# Chessbot_v5.net
KiCad netlist of a schematic drawn in EAGLE
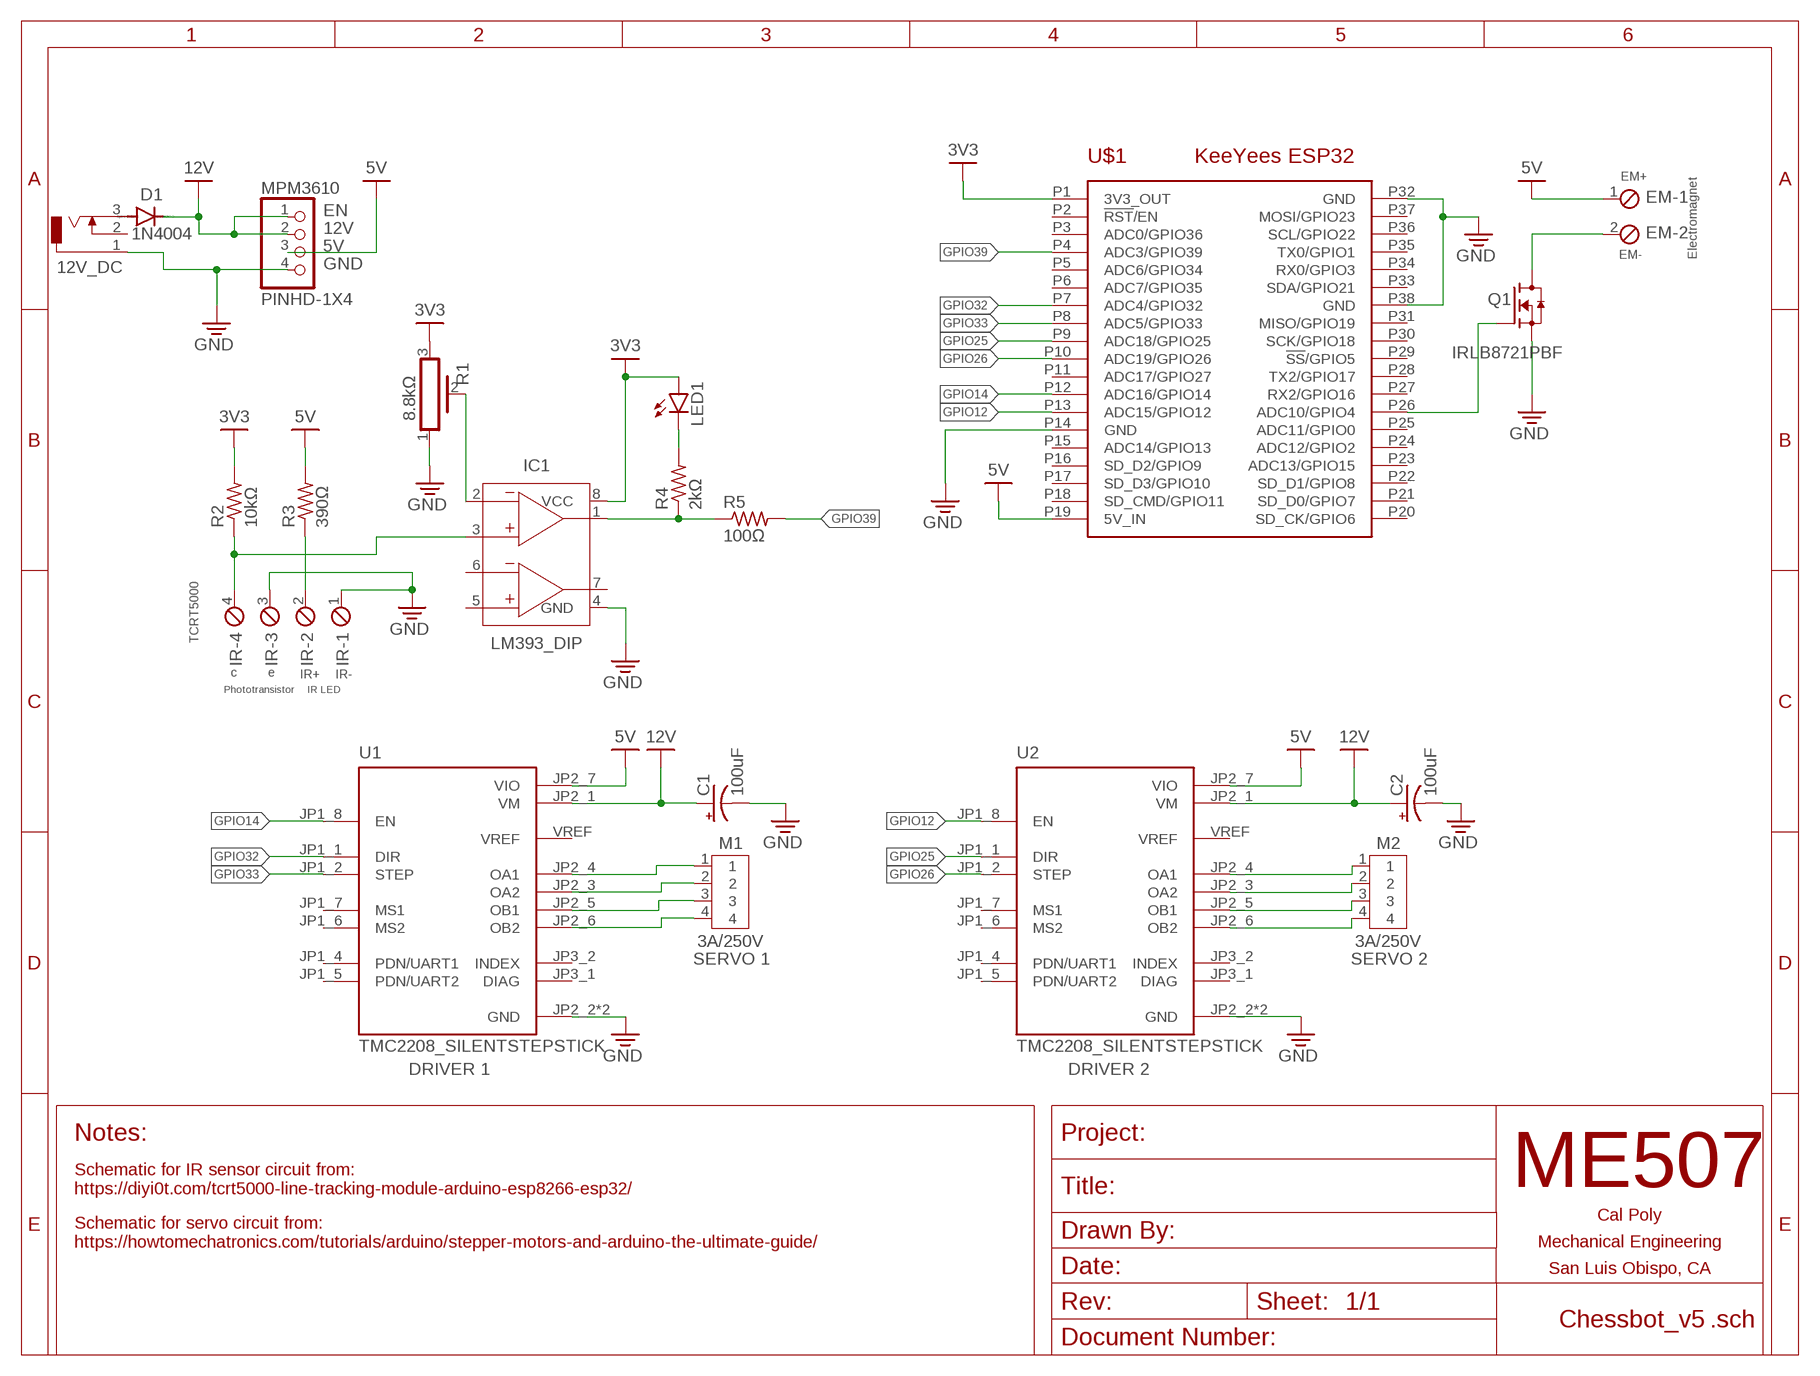
[diagram p0: schematic, sheet 1]

(export (version "E")
  (design (tool "Eeschema 10.0.6"))
  (components
    (comp (ref "12V_DC")
      (value "DCJ0303")
      (footprint "eagle-import:DCJ0303")
      (libsource (lib "eagle-import") (part "DCJ0303"))
    )
    (comp (ref "C1")
      (value "100uF")
      (footprint "eagle-import:E2,5-6")
      (libsource (lib "eagle-import") (part "CPOL-USE2.5-6"))
    )
    (comp (ref "C2")
      (value "100uF")
      (footprint "eagle-import:E2,5-6")
      (libsource (lib "eagle-import") (part "CPOL-USE2.5-6"))
    )
    (comp (ref "D1")
      (value "1N4004")
      (footprint "eagle-import:DO41-10")
      (libsource (lib "eagle-import") (part "1N4004"))
    )
    (comp (ref "EM")
      (value "SCREWTERM_2P_254")
      (footprint "eagle-import:2POL254")
      (libsource (lib "eagle-import") (part "SCREWTERM_2P_254"))
    )
    (comp (ref "IC1")
      (value "LM393_DIP")
      (footprint "eagle-import:DIP826W53P254L959H508Q8B")
      (fields (field (name "MANUFACTURER") "Generic"))
      (libsource (lib "eagle-import") (part "LM393_DIP"))
    )
    (comp (ref "IR")
      (value "SCREWTERM_4P_254")
      (footprint "eagle-import:4POL254")
      (libsource (lib "eagle-import") (part "SCREWTERM_4P_254"))
    )
    (comp (ref "LED1")
      (value "LEDSMT1206")
      (footprint "eagle-import:1206")
      (libsource (lib "eagle-import") (part "LEDSMT1206"))
    )
    (comp (ref "M1")
      (value "3A/250V")
      (footprint "eagle-import:B4B-XH-A")
      (fields (field (name "MANUFACTURER") "JST (XH connector)") (field (name "MPN") "B4B-XH-A"))
      (libsource (lib "eagle-import") (part "B4B-XH-A"))
    )
    (comp (ref "M2")
      (value "3A/250V")
      (footprint "eagle-import:B4B-XH-A")
      (fields (field (name "MANUFACTURER") "JST (XH connector)") (field (name "MPN") "B4B-XH-A"))
      (libsource (lib "eagle-import") (part "B4B-XH-A"))
    )
    (comp (ref "MPM3610")
      (value "PINHD-1X4")
      (footprint "eagle-import:1X04")
      (libsource (lib "eagle-import") (part "PINHD-1X4"))
    )
    (comp (ref "Q1")
      (value "IRLB8721PBF")
      (footprint "eagle-import:TO254P1067X483X2057-3")
      (fields (field (name "MF") "Infineon Technologies"))
      (libsource (lib "eagle-import") (part "IRLB8721PBF"))
    )
    (comp (ref "R1")
      (value "8.8kΩ")
      (footprint "eagle-import:PV36Z")
      (fields (field (name "MANUFACTURER") "BOURNS") (field (name "MPN") "PV36Z"))
      (libsource (lib "eagle-import") (part "PV36Z"))
    )
    (comp (ref "R2")
      (value "10kΩ")
      (footprint "eagle-import:R0805")
      (libsource (lib "eagle-import") (part "R-US_R0805"))
    )
    (comp (ref "R3")
      (value "390Ω")
      (footprint "eagle-import:R0805")
      (libsource (lib "eagle-import") (part "R-US_R0805"))
    )
    (comp (ref "R4")
      (value "2kΩ")
      (footprint "eagle-import:R0805")
      (libsource (lib "eagle-import") (part "R-US_R0805"))
    )
    (comp (ref "R5")
      (value "100Ω")
      (footprint "eagle-import:R0805")
      (libsource (lib "eagle-import") (part "R-US_R0805"))
    )
    (comp (ref "U$1")
      (value "KEEYEES_ESP32EXT")
      (footprint "eagle-import:KEEYEES_ESP32_EXTENDED")
      (libsource (lib "eagle-import") (part "KEEYEES_ESP32EXT"))
    )
    (comp (ref "U1")
      (value "TMC2208_SILENTSTEPSTICK")
      (footprint "eagle-import:MODULE_TMC2208_SILENTSTEPSTICK")
      (fields (field (name "MF") "Trinamic Motion") (field (name "MP") "TMC2208 SILENTSTEPSTICK"))
      (libsource (lib "eagle-import") (part "TMC2208_SILENTSTEPSTICK"))
    )
    (comp (ref "U2")
      (value "TMC2208_SILENTSTEPSTICK")
      (footprint "eagle-import:MODULE_TMC2208_SILENTSTEPSTICK")
      (fields (field (name "MF") "Trinamic Motion") (field (name "MP") "TMC2208 SILENTSTEPSTICK"))
      (libsource (lib "eagle-import") (part "TMC2208_SILENTSTEPSTICK"))
    )
  )
  (nets
    (net (code "1") (name "3V3") (class "Default")
      (node (ref "IC1") (pin "8") (pinfunction "VCC_8") (pintype "bidirectional"))
      (node (ref "LED1") (pin "A") (pinfunction "A_A") (pintype "passive"))
      (node (ref "R1") (pin "3") (pinfunction "P$3_3") (pintype "passive"))
      (node (ref "R2") (pin "2") (pinfunction "2_2") (pintype "passive"))
      (node (ref "U$1") (pin "P1") (pinfunction "3V3_OUT_P1") (pintype "power_in"))
    )
    (net (code "2") (name "5V") (class "Default")
      (node (ref "EM") (pin "1") (pinfunction "1_1") (pintype "passive"))
      (node (ref "MPM3610") (pin "3") (pinfunction "3_3") (pintype "passive"))
      (node (ref "R3") (pin "2") (pinfunction "2_2") (pintype "passive"))
      (node (ref "U$1") (pin "P19") (pinfunction "5V_IN_P19") (pintype "power_in"))
      (node (ref "U1") (pin "JP2_7") (pinfunction "VIO_JP2_7") (pintype "power_in"))
      (node (ref "U2") (pin "JP2_7") (pinfunction "VIO_JP2_7") (pintype "power_in"))
    )
    (net (code "3") (name "12V") (class "Default")
      (node (ref "C1") (pin "+") (pinfunction "+_+") (pintype "passive"))
      (node (ref "C2") (pin "+") (pinfunction "+_+") (pintype "passive"))
      (node (ref "D1") (pin "C") (pinfunction "C_C") (pintype "passive"))
      (node (ref "MPM3610") (pin "1") (pinfunction "1_1") (pintype "passive"))
      (node (ref "MPM3610") (pin "2") (pinfunction "2_2") (pintype "passive"))
      (node (ref "U1") (pin "JP2_1") (pinfunction "VM_JP2_1") (pintype "power_in"))
      (node (ref "U2") (pin "JP2_1") (pinfunction "VM_JP2_1") (pintype "power_in"))
    )
    (net (code "4") (name "GND") (class "Default")
      (node (ref "12V_DC") (pin "1") (pinfunction "1_1") (pintype "passive"))
      (node (ref "C1") (pin "-") (pinfunction "-_-") (pintype "passive"))
      (node (ref "C2") (pin "-") (pinfunction "-_-") (pintype "passive"))
      (node (ref "IC1") (pin "4") (pinfunction "GND_4") (pintype "bidirectional"))
      (node (ref "IR") (pin "1") (pinfunction "1_1") (pintype "passive"))
      (node (ref "IR") (pin "3") (pinfunction "1_3") (pintype "passive"))
      (node (ref "MPM3610") (pin "4") (pinfunction "4_4") (pintype "passive"))
      (node (ref "Q1") (pin "3") (pinfunction "S_3") (pintype "passive"))
      (node (ref "R1") (pin "1") (pinfunction "P$1_1") (pintype "passive"))
      (node (ref "U$1") (pin "P14") (pinfunction "GND_P14") (pintype "power_in"))
      (node (ref "U$1") (pin "P32") (pinfunction "GND_P32") (pintype "power_in"))
      (node (ref "U$1") (pin "P38") (pinfunction "GND_P38") (pintype "power_in"))
      (node (ref "U1") (pin "JP2_2") (pinfunction "GND_JP2_2") (pintype "power_in"))
      (node (ref "U1") (pin "JP2_8") (pinfunction "GND_JP2_8") (pintype "power_in"))
      (node (ref "U2") (pin "JP2_2") (pinfunction "GND_JP2_2") (pintype "power_in"))
      (node (ref "U2") (pin "JP2_8") (pinfunction "GND_JP2_8") (pintype "power_in"))
    )
    (net (code "5") (name "GPIO12") (class "Default")
      (node (ref "U$1") (pin "P13") (pinfunction "ADC15/GPIO12_P13") (pintype "bidirectional"))
      (node (ref "U2") (pin "JP1_8") (pinfunction "EN_JP1_8") (pintype "input"))
    )
    (net (code "6") (name "GPIO14") (class "Default")
      (node (ref "U$1") (pin "P12") (pinfunction "ADC16/GPIO14_P12") (pintype "bidirectional"))
      (node (ref "U1") (pin "JP1_8") (pinfunction "EN_JP1_8") (pintype "input"))
    )
    (net (code "7") (name "GPIO25") (class "Default")
      (node (ref "U$1") (pin "P9") (pinfunction "ADC18/GPIO25_P9") (pintype "bidirectional"))
      (node (ref "U2") (pin "JP1_1") (pinfunction "DIR_JP1_1") (pintype "input"))
    )
    (net (code "8") (name "GPIO26") (class "Default")
      (node (ref "U$1") (pin "P10") (pinfunction "ADC19/GPIO26_P10") (pintype "bidirectional"))
      (node (ref "U2") (pin "JP1_2") (pinfunction "STEP_JP1_2") (pintype "input"))
    )
    (net (code "9") (name "GPIO32") (class "Default")
      (node (ref "U$1") (pin "P7") (pinfunction "ADC4/GPIO32_P7") (pintype "bidirectional"))
      (node (ref "U1") (pin "JP1_1") (pinfunction "DIR_JP1_1") (pintype "input"))
    )
    (net (code "10") (name "GPIO33") (class "Default")
      (node (ref "U$1") (pin "P8") (pinfunction "ADC5/GPIO33_P8") (pintype "bidirectional"))
      (node (ref "U1") (pin "JP1_2") (pinfunction "STEP_JP1_2") (pintype "input"))
    )
    (net (code "11") (name "GPIO39") (class "Default")
      (node (ref "R5") (pin "2") (pinfunction "2_2") (pintype "passive"))
      (node (ref "U$1") (pin "P4") (pinfunction "ADC3/GPIO39_P4") (pintype "bidirectional"))
    )
    (net (code "12") (name "Net-(12V_DC-Pad3)") (class "Default")
      (node (ref "12V_DC") (pin "3") (pinfunction "3_3") (pintype "passive"))
      (node (ref "D1") (pin "A") (pinfunction "A_A") (pintype "passive"))
    )
    (net (code "13") (name "Net-(EMB-1)") (class "Default")
      (node (ref "EM") (pin "2") (pinfunction "1_2") (pintype "passive"))
      (node (ref "Q1") (pin "2") (pinfunction "D_2") (pintype "passive"))
    )
    (net (code "14") (name "Net-(IC1-+IN1)") (class "Default")
      (node (ref "IC1") (pin "3") (pinfunction "+IN1_3") (pintype "input"))
      (node (ref "IR") (pin "4") (pinfunction "1_4") (pintype "passive"))
      (node (ref "R2") (pin "1") (pinfunction "1_1") (pintype "passive"))
    )
    (net (code "15") (name "Net-(IC1--IN1)") (class "Default")
      (node (ref "IC1") (pin "2") (pinfunction "-IN1_2") (pintype "input"))
      (node (ref "R1") (pin "2") (pinfunction "P$2_2") (pintype "passive"))
    )
    (net (code "16") (name "Net-(IC1-OUT1)") (class "Default")
      (node (ref "IC1") (pin "1") (pinfunction "OUT1_1") (pintype "output"))
      (node (ref "R4") (pin "1") (pinfunction "1_1") (pintype "passive"))
      (node (ref "R5") (pin "1") (pinfunction "1_1") (pintype "passive"))
    )
    (net (code "17") (name "Net-(IRB-1)") (class "Default")
      (node (ref "IR") (pin "2") (pinfunction "1_2") (pintype "passive"))
      (node (ref "R3") (pin "1") (pinfunction "1_1") (pintype "passive"))
    )
    (net (code "18") (name "Net-(LED1-PadC)") (class "Default")
      (node (ref "LED1") (pin "C") (pinfunction "C_C") (pintype "passive"))
      (node (ref "R4") (pin "2") (pinfunction "2_2") (pintype "passive"))
    )
    (net (code "19") (name "Net-(Q1-G)") (class "Default")
      (node (ref "Q1") (pin "1") (pinfunction "G_1") (pintype "passive"))
      (node (ref "U$1") (pin "P26") (pinfunction "ADC10/GPIO4_P26") (pintype "bidirectional"))
    )
    (net (code "20") (name "Net-(U1-OA1)") (class "Default")
      (node (ref "M1") (pin "1") (pinfunction "1_1") (pintype "bidirectional"))
      (node (ref "U1") (pin "JP2_4") (pinfunction "OA1_JP2_4") (pintype "passive"))
    )
    (net (code "21") (name "Net-(U1-OA2)") (class "Default")
      (node (ref "M1") (pin "2") (pinfunction "2_2") (pintype "bidirectional"))
      (node (ref "U1") (pin "JP2_3") (pinfunction "OA2_JP2_3") (pintype "passive"))
    )
    (net (code "22") (name "Net-(U1-OB1)") (class "Default")
      (node (ref "M1") (pin "3") (pinfunction "3_3") (pintype "bidirectional"))
      (node (ref "U1") (pin "JP2_5") (pinfunction "OB1_JP2_5") (pintype "passive"))
    )
    (net (code "23") (name "Net-(U1-OB2)") (class "Default")
      (node (ref "M1") (pin "4") (pinfunction "4_4") (pintype "bidirectional"))
      (node (ref "U1") (pin "JP2_6") (pinfunction "OB2_JP2_6") (pintype "passive"))
    )
    (net (code "24") (name "Net-(U2-OA1)") (class "Default")
      (node (ref "M2") (pin "1") (pinfunction "1_1") (pintype "bidirectional"))
      (node (ref "U2") (pin "JP2_4") (pinfunction "OA1_JP2_4") (pintype "passive"))
    )
    (net (code "25") (name "Net-(U2-OA2)") (class "Default")
      (node (ref "M2") (pin "2") (pinfunction "2_2") (pintype "bidirectional"))
      (node (ref "U2") (pin "JP2_3") (pinfunction "OA2_JP2_3") (pintype "passive"))
    )
    (net (code "26") (name "Net-(U2-OB1)") (class "Default")
      (node (ref "M2") (pin "3") (pinfunction "3_3") (pintype "bidirectional"))
      (node (ref "U2") (pin "JP2_5") (pinfunction "OB1_JP2_5") (pintype "passive"))
    )
    (net (code "27") (name "Net-(U2-OB2)") (class "Default")
      (node (ref "M2") (pin "4") (pinfunction "4_4") (pintype "bidirectional"))
      (node (ref "U2") (pin "JP2_6") (pinfunction "OB2_JP2_6") (pintype "passive"))
    )
    (net (code "28") (name "unconnected-(12V_DC-Pad2)") (class "Default")
      (node (ref "12V_DC") (pin "2") (pinfunction "2_2") (pintype "passive"))
    )
    (net (code "29") (name "unconnected-(IC1-+IN2-Pad5)") (class "Default")
      (node (ref "IC1") (pin "5") (pinfunction "+IN2_5") (pintype "input"))
    )
    (net (code "30") (name "unconnected-(IC1--IN2-Pad6)") (class "Default")
      (node (ref "IC1") (pin "6") (pinfunction "-IN2_6") (pintype "input"))
    )
    (net (code "31") (name "unconnected-(IC1-OUT2-Pad7)") (class "Default")
      (node (ref "IC1") (pin "7") (pinfunction "OUT2_7") (pintype "output"))
    )
    (net (code "32") (name "unconnected-(U$1-ADC0{slash}GPIO36-PadP3)") (class "Default")
      (node (ref "U$1") (pin "P3") (pinfunction "ADC0/GPIO36_P3") (pintype "bidirectional"))
    )
    (net (code "33") (name "unconnected-(U$1-ADC6{slash}GPIO34-PadP5)") (class "Default")
      (node (ref "U$1") (pin "P5") (pinfunction "ADC6/GPIO34_P5") (pintype "bidirectional"))
    )
    (net (code "34") (name "unconnected-(U$1-ADC7{slash}GPIO35-PadP6)") (class "Default")
      (node (ref "U$1") (pin "P6") (pinfunction "ADC7/GPIO35_P6") (pintype "bidirectional"))
    )
    (net (code "35") (name "unconnected-(U$1-ADC11{slash}GPIO0-PadP25)") (class "Default")
      (node (ref "U$1") (pin "P25") (pinfunction "ADC11/GPIO0_P25") (pintype "bidirectional"))
    )
    (net (code "36") (name "unconnected-(U$1-ADC12{slash}GPIO2-PadP24)") (class "Default")
      (node (ref "U$1") (pin "P24") (pinfunction "ADC12/GPIO2_P24") (pintype "bidirectional"))
    )
    (net (code "37") (name "unconnected-(U$1-ADC13{slash}GPIO15-PadP23)") (class "Default")
      (node (ref "U$1") (pin "P23") (pinfunction "ADC13/GPIO15_P23") (pintype "bidirectional"))
    )
    (net (code "38") (name "unconnected-(U$1-ADC14{slash}GPIO13-PadP15)") (class "Default")
      (node (ref "U$1") (pin "P15") (pinfunction "ADC14/GPIO13_P15") (pintype "bidirectional"))
    )
    (net (code "39") (name "unconnected-(U$1-ADC17{slash}GPIO27-PadP11)") (class "Default")
      (node (ref "U$1") (pin "P11") (pinfunction "ADC17/GPIO27_P11") (pintype "bidirectional"))
    )
    (net (code "40") (name "unconnected-(U$1-MISO{slash}GPIO19-PadP31)") (class "Default")
      (node (ref "U$1") (pin "P31") (pinfunction "MISO/GPIO19_P31") (pintype "bidirectional"))
    )
    (net (code "41") (name "unconnected-(U$1-MOSI{slash}GPIO23-PadP37)") (class "Default")
      (node (ref "U$1") (pin "P37") (pinfunction "MOSI/GPIO23_P37") (pintype "bidirectional"))
    )
    (net (code "42") (name "unconnected-(U$1-RX0{slash}GPIO3-PadP34)") (class "Default")
      (node (ref "U$1") (pin "P34") (pinfunction "RX0/GPIO3_P34") (pintype "bidirectional"))
    )
    (net (code "43") (name "unconnected-(U$1-RX2{slash}GPIO16-PadP27)") (class "Default")
      (node (ref "U$1") (pin "P27") (pinfunction "RX2/GPIO16_P27") (pintype "bidirectional"))
    )
    (net (code "44") (name "unconnected-(U$1-SCK{slash}GPIO18-PadP30)") (class "Default")
      (node (ref "U$1") (pin "P30") (pinfunction "SCK/GPIO18_P30") (pintype "bidirectional"))
    )
    (net (code "45") (name "unconnected-(U$1-SCL{slash}GPIO22-PadP36)") (class "Default")
      (node (ref "U$1") (pin "P36") (pinfunction "SCL/GPIO22_P36") (pintype "bidirectional"))
    )
    (net (code "46") (name "unconnected-(U$1-SDA{slash}GPIO21-PadP33)") (class "Default")
      (node (ref "U$1") (pin "P33") (pinfunction "SDA/GPIO21_P33") (pintype "bidirectional"))
    )
    (net (code "47") (name "unconnected-(U$1-SD_CK{slash}GPIO6-PadP20)") (class "Default")
      (node (ref "U$1") (pin "P20") (pinfunction "SD_CK/GPIO6_P20") (pintype "bidirectional"))
    )
    (net (code "48") (name "unconnected-(U$1-SD_CMD{slash}GPIO11-PadP18)") (class "Default")
      (node (ref "U$1") (pin "P18") (pinfunction "SD_CMD/GPIO11_P18") (pintype "bidirectional"))
    )
    (net (code "49") (name "unconnected-(U$1-SD_D0{slash}GPIO7-PadP21)") (class "Default")
      (node (ref "U$1") (pin "P21") (pinfunction "SD_D0/GPIO7_P21") (pintype "bidirectional"))
    )
    (net (code "50") (name "unconnected-(U$1-SD_D1{slash}GPIO8-PadP22)") (class "Default")
      (node (ref "U$1") (pin "P22") (pinfunction "SD_D1/GPIO8_P22") (pintype "bidirectional"))
    )
    (net (code "51") (name "unconnected-(U$1-SD_D2{slash}GPIO9-PadP16)") (class "Default")
      (node (ref "U$1") (pin "P16") (pinfunction "SD_D2/GPIO9_P16") (pintype "bidirectional"))
    )
    (net (code "52") (name "unconnected-(U$1-SD_D3{slash}GPIO10-PadP17)") (class "Default")
      (node (ref "U$1") (pin "P17") (pinfunction "SD_D3/GPIO10_P17") (pintype "bidirectional"))
    )
    (net (code "53") (name "unconnected-(U$1-TX0{slash}GPIO1-PadP35)") (class "Default")
      (node (ref "U$1") (pin "P35") (pinfunction "TX0/GPIO1_P35") (pintype "bidirectional"))
    )
    (net (code "54") (name "unconnected-(U$1-TX2{slash}GPIO17-PadP28)") (class "Default")
      (node (ref "U$1") (pin "P28") (pinfunction "TX2/GPIO17_P28") (pintype "bidirectional"))
    )
    (net (code "55") (name "unconnected-(U$1-~{RST}{slash}EN-PadP2)") (class "Default")
      (node (ref "U$1") (pin "P2") (pinfunction "~{RST}/EN_P2") (pintype "input"))
    )
    (net (code "56") (name "unconnected-(U$1-~{SS}{slash}GPIO5-PadP29)") (class "Default")
      (node (ref "U$1") (pin "P29") (pinfunction "~{SS}/GPIO5_P29") (pintype "bidirectional"))
    )
    (net (code "57") (name "unconnected-(U1-DIAG-PadJP3_1)") (class "Default")
      (node (ref "U1") (pin "JP3_1") (pinfunction "DIAG_JP3_1") (pintype "output"))
    )
    (net (code "58") (name "unconnected-(U1-INDEX-PadJP3_2)") (class "Default")
      (node (ref "U1") (pin "JP3_2") (pinfunction "INDEX_JP3_2") (pintype "output"))
    )
    (net (code "59") (name "unconnected-(U1-MS1-PadJP1_7)") (class "Default")
      (node (ref "U1") (pin "JP1_7") (pinfunction "MS1_JP1_7") (pintype "input"))
    )
    (net (code "60") (name "unconnected-(U1-MS2-PadJP1_6)") (class "Default")
      (node (ref "U1") (pin "JP1_6") (pinfunction "MS2_JP1_6") (pintype "input"))
    )
    (net (code "61") (name "unconnected-(U1-PDN{slash}UART1-PadJP1_4)") (class "Default")
      (node (ref "U1") (pin "JP1_4") (pinfunction "PDN/UART1_JP1_4") (pintype "bidirectional"))
    )
    (net (code "62") (name "unconnected-(U1-PDN{slash}UART2-PadJP1_5)") (class "Default")
      (node (ref "U1") (pin "JP1_5") (pinfunction "PDN/UART2_JP1_5") (pintype "bidirectional"))
    )
    (net (code "63") (name "unconnected-(U1-PadVREF)") (class "Default")
      (node (ref "U1") (pin "VREF") (pinfunction "VREF_VREF") (pintype "passive"))
    )
    (net (code "64") (name "unconnected-(U2-DIAG-PadJP3_1)") (class "Default")
      (node (ref "U2") (pin "JP3_1") (pinfunction "DIAG_JP3_1") (pintype "output"))
    )
    (net (code "65") (name "unconnected-(U2-INDEX-PadJP3_2)") (class "Default")
      (node (ref "U2") (pin "JP3_2") (pinfunction "INDEX_JP3_2") (pintype "output"))
    )
    (net (code "66") (name "unconnected-(U2-MS1-PadJP1_7)") (class "Default")
      (node (ref "U2") (pin "JP1_7") (pinfunction "MS1_JP1_7") (pintype "input"))
    )
    (net (code "67") (name "unconnected-(U2-MS2-PadJP1_6)") (class "Default")
      (node (ref "U2") (pin "JP1_6") (pinfunction "MS2_JP1_6") (pintype "input"))
    )
    (net (code "68") (name "unconnected-(U2-PDN{slash}UART1-PadJP1_4)") (class "Default")
      (node (ref "U2") (pin "JP1_4") (pinfunction "PDN/UART1_JP1_4") (pintype "bidirectional"))
    )
    (net (code "69") (name "unconnected-(U2-PDN{slash}UART2-PadJP1_5)") (class "Default")
      (node (ref "U2") (pin "JP1_5") (pinfunction "PDN/UART2_JP1_5") (pintype "bidirectional"))
    )
    (net (code "70") (name "unconnected-(U2-PadVREF)") (class "Default")
      (node (ref "U2") (pin "VREF") (pinfunction "VREF_VREF") (pintype "passive"))
    )
  )
)
